# DAC_DAC084S085_SPI.net
KiCad netlist of a schematic drawn in Altium Designer
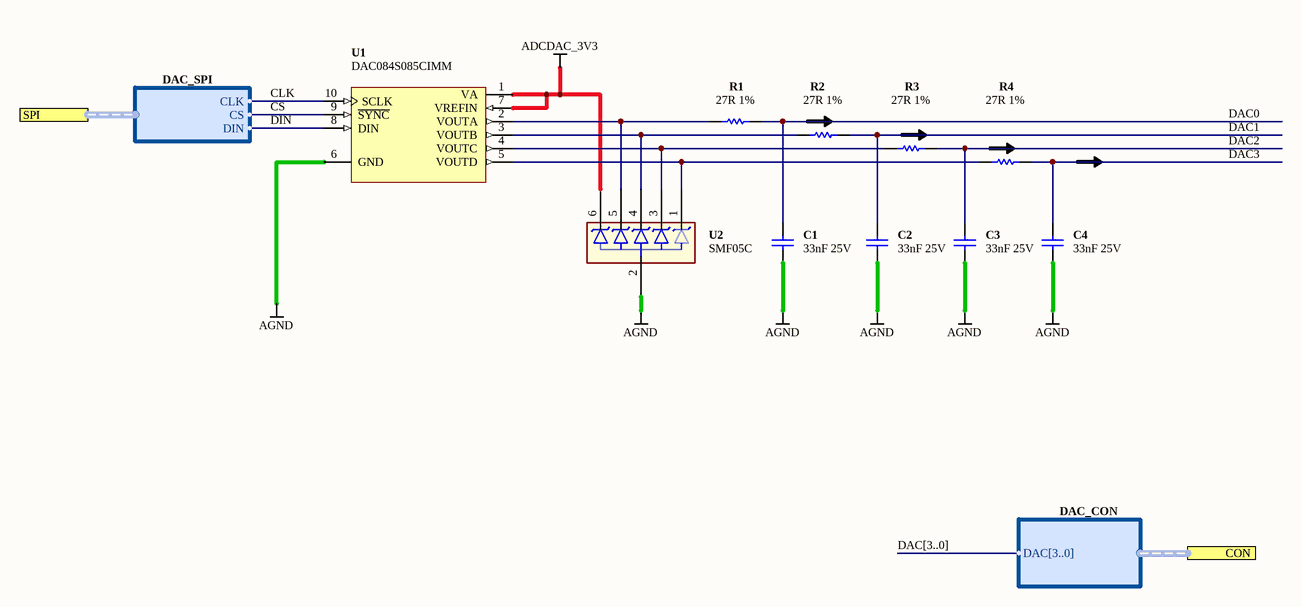
[diagram p0: DAC_DAC084S085_SPI.SchDoc]

(export (version "E")
  (design (tool "Eeschema 10.0.6"))
  (components
    (comp (ref "C1")
      (value "33nF 25V")
      (footprint "CAPC1005-STAR")
      (description "Capacitor, Ceramic, 33nF 10% 25V 0402 (1005) X7R")
      (fields (field (name "TOLERANCE") "10 %"))
      (libsource (lib "AltiumDesignLibrary") (part "CAP-NP"))
    )
    (comp (ref "C2")
      (value "33nF 25V")
      (footprint "CAPC1005-STAR")
      (description "Capacitor, Ceramic, 33nF 10% 25V 0402 (1005) X7R")
      (fields (field (name "TOLERANCE") "10 %"))
      (libsource (lib "AltiumDesignLibrary") (part "CAP-NP"))
    )
    (comp (ref "C3")
      (value "33nF 25V")
      (footprint "CAPC1005-STAR")
      (description "Capacitor, Ceramic, 33nF 10% 25V 0402 (1005) X7R")
      (fields (field (name "TOLERANCE") "10 %"))
      (libsource (lib "AltiumDesignLibrary") (part "CAP-NP"))
    )
    (comp (ref "C4")
      (value "33nF 25V")
      (footprint "CAPC1005-STAR")
      (description "Capacitor, Ceramic, 33nF 10% 25V 0402 (1005) X7R")
      (fields (field (name "TOLERANCE") "10 %"))
      (libsource (lib "AltiumDesignLibrary") (part "CAP-NP"))
    )
    (comp (ref "R1")
      (value "27R 1%")
      (footprint "RESC1005-STAR")
      (description "Resistor, 27R 1% 0402 (1005)")
      (fields (field (name "TOLERANCE") "1 %"))
      (libsource (lib "AltiumDesignLibrary") (part "RES"))
    )
    (comp (ref "R2")
      (value "27R 1%")
      (footprint "RESC1005-STAR")
      (description "Resistor, 27R 1% 0402 (1005)")
      (fields (field (name "TOLERANCE") "1 %"))
      (libsource (lib "AltiumDesignLibrary") (part "RES"))
    )
    (comp (ref "R3")
      (value "27R 1%")
      (footprint "RESC1005-STAR")
      (description "Resistor, 27R 1% 0402 (1005)")
      (fields (field (name "TOLERANCE") "1 %"))
      (libsource (lib "AltiumDesignLibrary") (part "RES"))
    )
    (comp (ref "R4")
      (value "27R 1%")
      (footprint "RESC1005-STAR")
      (description "Resistor, 27R 1% 0402 (1005)")
      (fields (field (name "TOLERANCE") "1 %"))
      (libsource (lib "AltiumDesignLibrary") (part "RES"))
    )
    (comp (ref "U1")
      (value "DAC084S085CIMM")
      (footprint "TSSOP50P490-10AN")
      (description "DAC084S085CIMM, Quad 8-bit, Single 2.7V to 5.5V rail-to-rail output")
      (libsource (lib "AltiumDesignLibrary") (part "DAC084S085CIMM"))
    )
    (comp (ref "U2")
      (value "SMF05C")
      (footprint "SC70_6L")
      (description "TVS Diode Array  For ESD and Latch-Up Protection")
      (libsource (lib "AltiumDesignLibrary") (part "SMF05C"))
    )
  )
  (nets
    (net (code "3") (name "/CLK") (class "Default")
      (node (ref "U1") (pin "10") (pinfunction "SCLK_10") (pintype "input"))
    )
    (net (code "5") (name "/CS") (class "Default")
      (node (ref "U1") (pin "9") (pinfunction "~{SYNC}_9") (pintype "input"))
    )
    (net (code "6") (name "/DAC0") (class "Default")
      (node (ref "C1") (pin "1") (pinfunction "1_1") (pintype "passive"))
      (node (ref "R1") (pin "1") (pinfunction "1_1") (pintype "passive"))
    )
    (net (code "7") (name "/DAC1") (class "Default")
      (node (ref "C2") (pin "1") (pinfunction "1_1") (pintype "passive"))
      (node (ref "R2") (pin "1") (pinfunction "1_1") (pintype "passive"))
    )
    (net (code "8") (name "/DAC2") (class "Default")
      (node (ref "C3") (pin "1") (pinfunction "1_1") (pintype "passive"))
      (node (ref "R3") (pin "1") (pinfunction "1_1") (pintype "passive"))
    )
    (net (code "9") (name "/DAC3") (class "Default")
      (node (ref "C4") (pin "1") (pinfunction "1_1") (pintype "passive"))
      (node (ref "R4") (pin "1") (pinfunction "1_1") (pintype "passive"))
    )
    (net (code "10") (name "/DIN") (class "Default")
      (node (ref "U1") (pin "8") (pinfunction "DIN_8") (pintype "input"))
    )
    (net (code "13") (name "ADCDAC_3V3") (class "Default")
      (node (ref "U1") (pin "1") (pinfunction "VA_1") (pintype "power_in"))
      (node (ref "U1") (pin "7") (pinfunction "VREFIN_7") (pintype "input"))
      (node (ref "U2") (pin "6") (pinfunction "6_6") (pintype "passive"))
    )
    (net (code "14") (name "AGND") (class "Default")
      (node (ref "C1") (pin "2") (pinfunction "2_2") (pintype "passive"))
      (node (ref "C2") (pin "2") (pinfunction "2_2") (pintype "passive"))
      (node (ref "C3") (pin "2") (pinfunction "2_2") (pintype "passive"))
      (node (ref "C4") (pin "2") (pinfunction "2_2") (pintype "passive"))
      (node (ref "U1") (pin "6") (pinfunction "GND_6") (pintype "power_in"))
      (node (ref "U2") (pin "2") (pinfunction "2_2") (pintype "passive"))
    )
    (net (code "15") (name "Net-(U1-VOUTA)") (class "Default")
      (node (ref "R1") (pin "2") (pinfunction "2_2") (pintype "passive"))
      (node (ref "U1") (pin "2") (pinfunction "VOUTA_2") (pintype "output"))
      (node (ref "U2") (pin "5") (pinfunction "5_5") (pintype "passive"))
    )
    (net (code "16") (name "Net-(U1-VOUTB)") (class "Default")
      (node (ref "R2") (pin "2") (pinfunction "2_2") (pintype "passive"))
      (node (ref "U1") (pin "3") (pinfunction "VOUTB_3") (pintype "output"))
      (node (ref "U2") (pin "4") (pinfunction "4_4") (pintype "passive"))
    )
    (net (code "17") (name "Net-(U1-VOUTC)") (class "Default")
      (node (ref "R3") (pin "2") (pinfunction "2_2") (pintype "passive"))
      (node (ref "U1") (pin "4") (pinfunction "VOUTC_4") (pintype "output"))
      (node (ref "U2") (pin "3") (pinfunction "3_3") (pintype "passive"))
    )
    (net (code "18") (name "Net-(U1-VOUTD)") (class "Default")
      (node (ref "R4") (pin "2") (pinfunction "2_2") (pintype "passive"))
      (node (ref "U1") (pin "5") (pinfunction "VOUTD_5") (pintype "output"))
      (node (ref "U2") (pin "1") (pinfunction "1_1") (pintype "passive"))
    )
  )
)
